# micro-ATMEGA32M1.net
KiCad netlist of a schematic drawn in Altium Designer
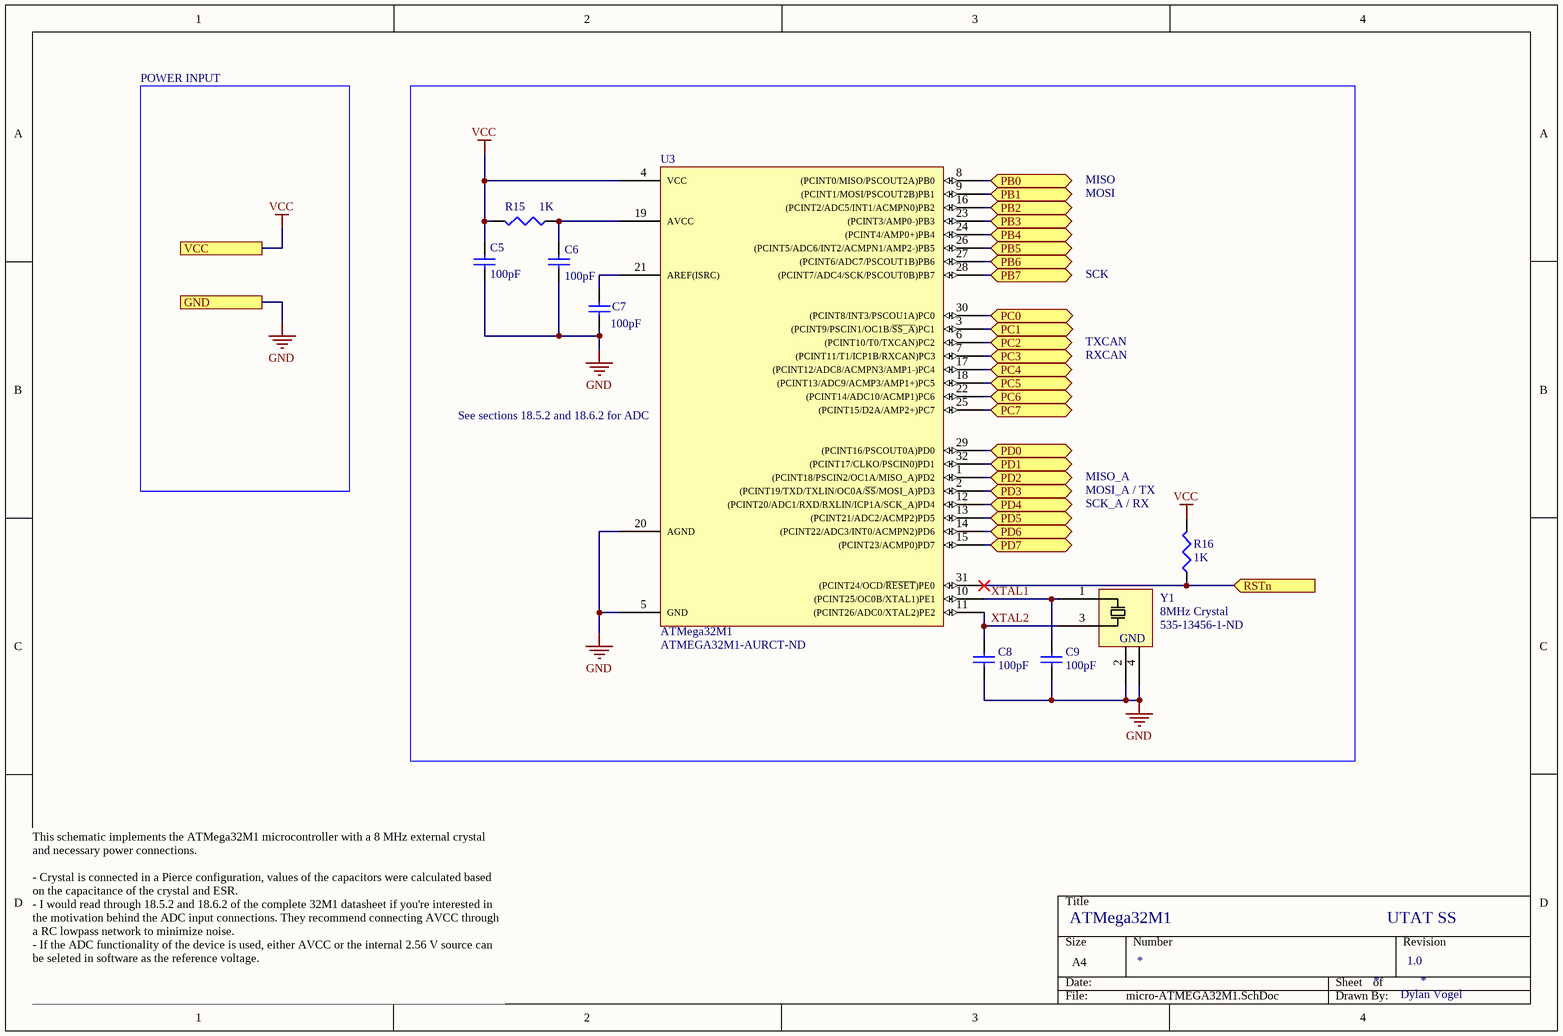
[diagram p0: micro-ATMEGA32M1.SchDoc]

(export (version "E")
  (design (tool "Eeschema 10.0.6"))
  (components
    (comp (ref "C5")
      (value "100pF")
      (footprint "C1206")
      (description "Capacitor (Semiconductor SIM Model)")
      (fields (field (name "Comment") "Cap Semi") (field (name "PUBLISHER") "Altium Limited"))
      (libsource (lib "Miscellaneous Devices") (part "Cap Semi"))
    )
    (comp (ref "C6")
      (value "100pF")
      (footprint "C1206")
      (description "Capacitor (Semiconductor SIM Model)")
      (fields (field (name "Comment") "Cap Semi") (field (name "PUBLISHER") "Altium Limited"))
      (libsource (lib "Miscellaneous Devices") (part "Cap Semi"))
    )
    (comp (ref "C7")
      (value "100pF")
      (footprint "C1206")
      (description "Capacitor (Semiconductor SIM Model)")
      (fields (field (name "Comment") "Cap Semi") (field (name "PUBLISHER") "Altium Limited"))
      (libsource (lib "Miscellaneous Devices") (part "Cap Semi"))
    )
    (comp (ref "C8")
      (value "100pF")
      (footprint "C1206")
      (description "Capacitor (Semiconductor SIM Model)")
      (fields (field (name "Comment") "Cap Semi") (field (name "PUBLISHER") "Altium Limited"))
      (libsource (lib "Miscellaneous Devices") (part "Cap Semi"))
    )
    (comp (ref "C9")
      (value "100pF")
      (footprint "C1206")
      (description "Capacitor (Semiconductor SIM Model)")
      (fields (field (name "Comment") "Cap Semi") (field (name "PUBLISHER") "Altium Limited"))
      (libsource (lib "Miscellaneous Devices") (part "Cap Semi"))
    )
    (comp (ref "R15")
      (value "1K")
      (footprint "J1-0603")
      (description "Resistor")
      (fields (field (name "Comment") "Res3") (field (name "PUBLISHER") "Altium Limited"))
      (libsource (lib "Miscellaneous Devices") (part "Res3"))
    )
    (comp (ref "R16")
      (value "1K")
      (footprint "J1-0603")
      (description "Resistor")
      (fields (field (name "Comment") "Res3") (field (name "PUBLISHER") "Altium Limited"))
      (libsource (lib "Miscellaneous Devices") (part "Res3"))
    )
    (comp (ref "U3")
      (value "ATMega32M1")
      (footprint "QFP80P900X900X120-32")
      (description "Atmel 8-bit AVR microcontroller.")
      (fields (field (name "SUPPLIER PART NUMBER 1") "ATMEGA32M1-AURCT-ND"))
      (libsource (lib "heron-general") (part "ATMega32M1"))
    )
    (comp (ref "Y1")
      (value "8MHz Crystal")
      (footprint "OSCSC500X320X110-4N")
      (description "8MHz Abracom 4-pin crystal.")
      (fields (field (name "SUPPLIER PART NUMBER 1") "535-13456-1-ND"))
      (libsource (lib "heron-general") (part "AMB3B-8MHz"))
    )
  )
  (nets
    (net (code "1") (name "/PB0") (class "Default")
      (node (ref "U3") (pin "8") (pinfunction "(PCINT0/MISO/PSCOUT2A)PB0_8") (pintype "bidirectional"))
    )
    (net (code "2") (name "/PB1") (class "Default")
      (node (ref "U3") (pin "9") (pinfunction "(PCINT1/MOSI/PSCOUT2B)PB1_9") (pintype "bidirectional"))
    )
    (net (code "3") (name "/PB2") (class "Default")
      (node (ref "U3") (pin "16") (pinfunction "(PCINT2/ADC5/INT1/ACMPN0)PB2_16") (pintype "bidirectional"))
    )
    (net (code "4") (name "/PB3") (class "Default")
      (node (ref "U3") (pin "23") (pinfunction "(PCINT3/AMP0-)PB3_23") (pintype "bidirectional"))
    )
    (net (code "5") (name "/PB4") (class "Default")
      (node (ref "U3") (pin "24") (pinfunction "(PCINT4/AMP0+)PB4_24") (pintype "bidirectional"))
    )
    (net (code "6") (name "/PB5") (class "Default")
      (node (ref "U3") (pin "26") (pinfunction "(PCINT5/ADC6/INT2/ACMPN1/AMP2-)PB5_26") (pintype "bidirectional"))
    )
    (net (code "7") (name "/PB6") (class "Default")
      (node (ref "U3") (pin "27") (pinfunction "(PCINT6/ADC7/PSCOUT1B)PB6_27") (pintype "bidirectional"))
    )
    (net (code "8") (name "/PB7") (class "Default")
      (node (ref "U3") (pin "28") (pinfunction "(PCINT7/ADC4/SCK/PSCOUT0B)PB7_28") (pintype "bidirectional"))
    )
    (net (code "9") (name "/PC0") (class "Default")
      (node (ref "U3") (pin "30") (pinfunction "(PCINT8/INT3/PSCOU1A)PC0_30") (pintype "bidirectional"))
    )
    (net (code "10") (name "/PC1") (class "Default")
      (node (ref "U3") (pin "3") (pinfunction "(PCINT9/PSCIN1/OC1B/~{SS_A})PC1_3") (pintype "bidirectional"))
    )
    (net (code "11") (name "/PC2") (class "Default")
      (node (ref "U3") (pin "6") (pinfunction "(PCINT10/T0/TXCAN)PC2_6") (pintype "bidirectional"))
    )
    (net (code "12") (name "/PC3") (class "Default")
      (node (ref "U3") (pin "7") (pinfunction "(PCINT11/T1/ICP1B/RXCAN)PC3_7") (pintype "bidirectional"))
    )
    (net (code "13") (name "/PC4") (class "Default")
      (node (ref "U3") (pin "17") (pinfunction "(PCINT12/ADC8/ACMPN3/AMP1-)PC4_17") (pintype "bidirectional"))
    )
    (net (code "14") (name "/PC5") (class "Default")
      (node (ref "U3") (pin "18") (pinfunction "(PCINT13/ADC9/ACMP3/AMP1+)PC5_18") (pintype "bidirectional"))
    )
    (net (code "15") (name "/PC6") (class "Default")
      (node (ref "U3") (pin "22") (pinfunction "(PCINT14/ADC10/ACMP1)PC6_22") (pintype "bidirectional"))
    )
    (net (code "16") (name "/PC7") (class "Default")
      (node (ref "U3") (pin "25") (pinfunction "(PCINT15/D2A/AMP2+)PC7_25") (pintype "bidirectional"))
    )
    (net (code "17") (name "/PD0") (class "Default")
      (node (ref "U3") (pin "29") (pinfunction "(PCINT16/PSCOUT0A)PD0_29") (pintype "bidirectional"))
    )
    (net (code "18") (name "/PD1") (class "Default")
      (node (ref "U3") (pin "32") (pinfunction "(PCINT17/CLKO/PSCIN0)PD1_32") (pintype "bidirectional"))
    )
    (net (code "19") (name "/PD2") (class "Default")
      (node (ref "U3") (pin "1") (pinfunction "(PCINT18/PSCIN2/OC1A/MISO_A)PD2_1") (pintype "bidirectional"))
    )
    (net (code "20") (name "/PD3") (class "Default")
      (node (ref "U3") (pin "2") (pinfunction "(PCINT19/TXD/TXLIN/OC0A/~{SS}/MOSI_A)PD3_2") (pintype "bidirectional"))
    )
    (net (code "21") (name "/PD4") (class "Default")
      (node (ref "U3") (pin "12") (pinfunction "(PCINT20/ADC1/RXD/RXLIN/ICP1A/SCK_A)PD4_12") (pintype "bidirectional"))
    )
    (net (code "22") (name "/PD5") (class "Default")
      (node (ref "U3") (pin "13") (pinfunction "(PCINT21/ADC2/ACMP2)PD5_13") (pintype "bidirectional"))
    )
    (net (code "23") (name "/PD6") (class "Default")
      (node (ref "U3") (pin "14") (pinfunction "(PCINT22/ADC3/INT0/ACMPN2)PD6_14") (pintype "bidirectional"))
    )
    (net (code "24") (name "/PD7") (class "Default")
      (node (ref "U3") (pin "15") (pinfunction "(PCINT23/ACMP0)PD7_15") (pintype "bidirectional"))
    )
    (net (code "25") (name "/RSTn") (class "Default")
      (node (ref "R16") (pin "1") (pinfunction "1_1") (pintype "passive"))
      (node (ref "U3") (pin "31") (pinfunction "(PCINT24/OCD/~{RESET})PE0_31") (pintype "bidirectional"))
    )
    (net (code "26") (name "/XTAL1") (class "Default")
      (node (ref "C9") (pin "2") (pinfunction "2_2") (pintype "passive"))
      (node (ref "U3") (pin "10") (pinfunction "(PCINT25/OC0B/XTAL1)PE1_10") (pintype "bidirectional"))
      (node (ref "Y1") (pin "1") (pinfunction "IN_1") (pintype "passive"))
    )
    (net (code "27") (name "/XTAL2") (class "Default")
      (node (ref "C8") (pin "2") (pinfunction "2_2") (pintype "passive"))
      (node (ref "U3") (pin "11") (pinfunction "(PCINT26/ADC0/XTAL2)PE2_11") (pintype "bidirectional"))
      (node (ref "Y1") (pin "3") (pinfunction "IN_3") (pintype "passive"))
    )
    (net (code "28") (name "GND") (class "Default")
      (node (ref "C5") (pin "1") (pinfunction "1_1") (pintype "passive"))
      (node (ref "C6") (pin "1") (pinfunction "1_1") (pintype "passive"))
      (node (ref "C7") (pin "2") (pinfunction "2_2") (pintype "passive"))
      (node (ref "C8") (pin "1") (pinfunction "1_1") (pintype "passive"))
      (node (ref "C9") (pin "1") (pinfunction "1_1") (pintype "passive"))
      (node (ref "U3") (pin "20") (pinfunction "AGND_20") (pintype "power_in"))
      (node (ref "U3") (pin "5") (pinfunction "GND_5") (pintype "power_in"))
      (node (ref "Y1") (pin "2") (pinfunction "5_2") (pintype "passive"))
      (node (ref "Y1") (pin "4") (pinfunction "4_4") (pintype "passive"))
    )
    (net (code "29") (name "Net-(U3-AREF(ISRC))") (class "Default")
      (node (ref "C7") (pin "1") (pinfunction "1_1") (pintype "passive"))
      (node (ref "U3") (pin "21") (pinfunction "AREF(ISRC)_21") (pintype "power_in"))
    )
    (net (code "30") (name "Net-(U3-AVCC)") (class "Default")
      (node (ref "C6") (pin "2") (pinfunction "2_2") (pintype "passive"))
      (node (ref "R15") (pin "1") (pinfunction "1_1") (pintype "passive"))
      (node (ref "U3") (pin "19") (pinfunction "AVCC_19") (pintype "power_in"))
    )
    (net (code "31") (name "VCC") (class "Default")
      (node (ref "C5") (pin "2") (pinfunction "2_2") (pintype "passive"))
      (node (ref "R15") (pin "2") (pinfunction "2_2") (pintype "passive"))
      (node (ref "R16") (pin "2") (pinfunction "2_2") (pintype "passive"))
      (node (ref "U3") (pin "4") (pinfunction "VCC_4") (pintype "power_in"))
    )
  )
)
